# Schematic.net
KiCad netlist of a schematic drawn in EAGLE
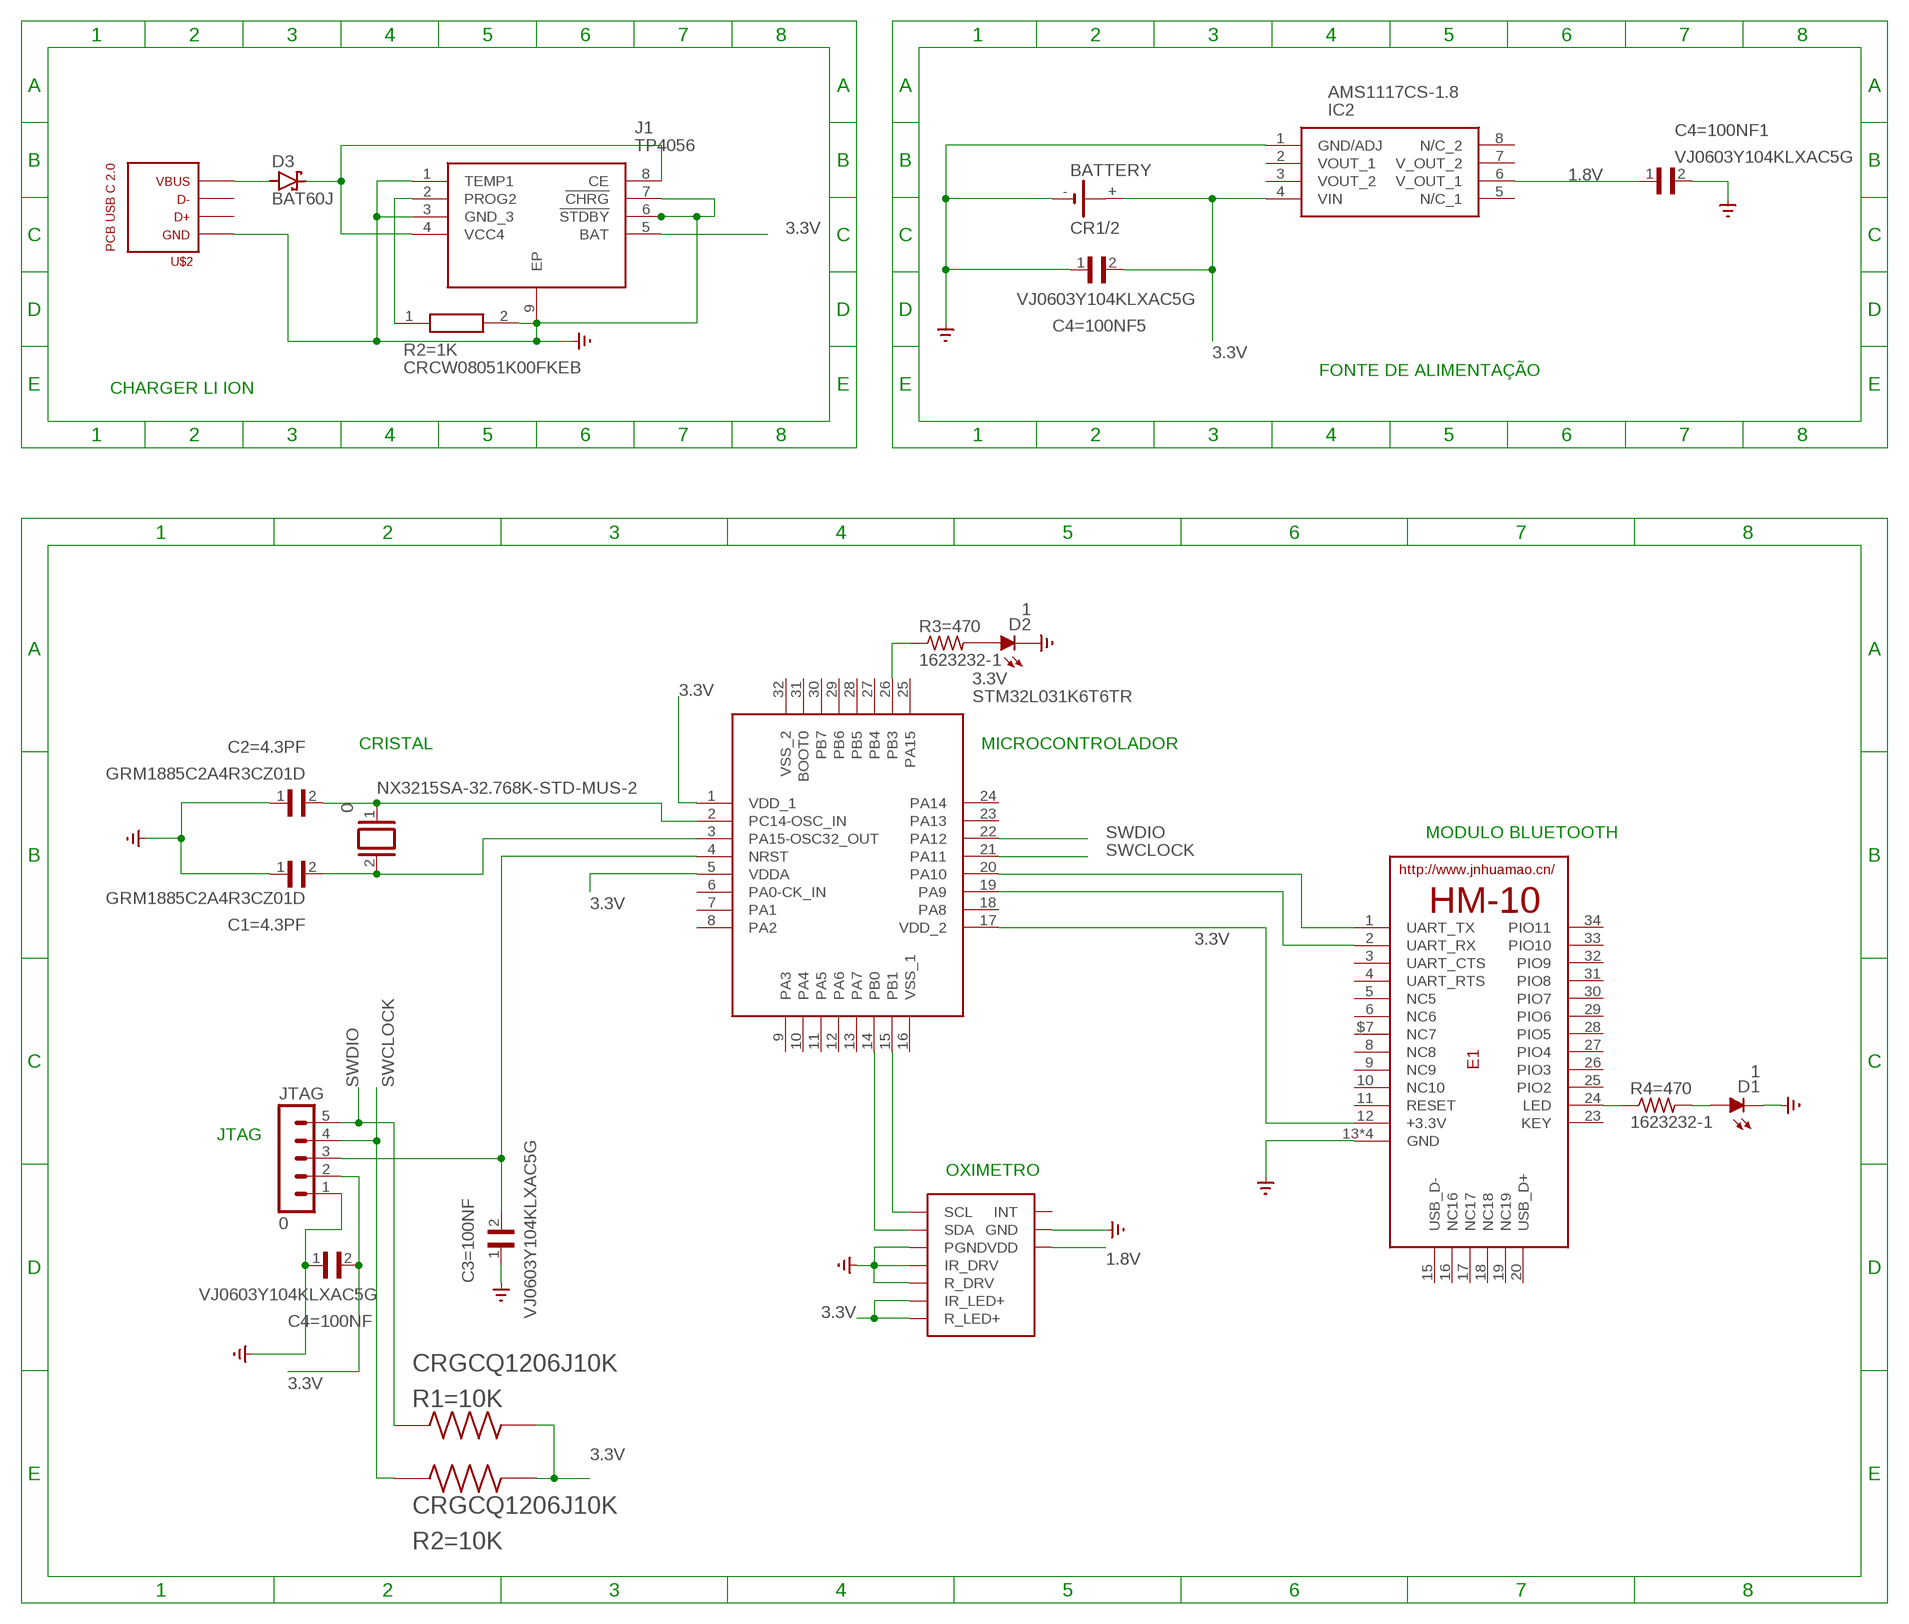
[diagram p0: schematic, sheet 1]

(export (version "E")
  (design (tool "Eeschema 10.0.6"))
  (components
    (comp (ref "3.3V")
      (value "STM32L031K6T6TR")
      (footprint "eagle-import:QFP80P900X900X160-32N")
      (fields (field (name "MOUSER_PART_NUMBER") "511-STM32L031K6T6TR"))
      (libsource (lib "eagle-import") (part "STM32L031K6T6TR"))
    )
    (comp (ref "BATTERY")
      (value "CR1/2")
      (footprint "eagle-import:CR1_2")
      (libsource (lib "eagle-import") (part "CR1/2"))
    )
    (comp (ref "C1=4.3PF")
      (value "GRM1885C2A4R3CZ01D")
      (footprint "eagle-import:CAPC1608X90N")
      (fields (field (name "MF") "Murata"))
      (libsource (lib "eagle-import") (part "GRM1885C2A4R3CZ01D"))
    )
    (comp (ref "C2=4.3PF")
      (value "GRM1885C2A4R3CZ01D")
      (footprint "eagle-import:CAPC1608X90N")
      (fields (field (name "MF") "Murata"))
      (libsource (lib "eagle-import") (part "GRM1885C2A4R3CZ01D"))
    )
    (comp (ref "C3=100NF")
      (value "VJ0603Y104KLXAC5G")
      (footprint "eagle-import:CAPC1608X92N")
      (fields (field (name "MF") "Vishay"))
      (libsource (lib "eagle-import") (part "VJ0603Y104KLXAC5G"))
    )
    (comp (ref "C4=100NF")
      (value "VJ0603Y104KLXAC5G")
      (footprint "eagle-import:CAPC1608X92N")
      (fields (field (name "MF") "Vishay"))
      (libsource (lib "eagle-import") (part "VJ0603Y104KLXAC5G"))
    )
    (comp (ref "C4=100NF1")
      (value "VJ0603Y104KLXAC5G")
      (footprint "eagle-import:CAPC1608X92N")
      (fields (field (name "MF") "Vishay"))
      (libsource (lib "eagle-import") (part "VJ0603Y104KLXAC5G"))
    )
    (comp (ref "C4=100NF5")
      (value "VJ0603Y104KLXAC5G")
      (footprint "eagle-import:CAPC1608X92N")
      (fields (field (name "MF") "Vishay"))
      (libsource (lib "eagle-import") (part "VJ0603Y104KLXAC5G"))
    )
    (comp (ref "D1")
      (value "1")
      (footprint "eagle-import:LED_CHIP-LED0603MP")
      (libsource (lib "eagle-import") (part "LED_LEDCHIP-LED0603MP"))
    )
    (comp (ref "D2")
      (value "1")
      (footprint "eagle-import:LED_CHIP-LED0603MP")
      (libsource (lib "eagle-import") (part "LED_LEDCHIP-LED0603MP"))
    )
    (comp (ref "D3")
      (value "BAT60J")
      (footprint "eagle-import:SOD323_ST")
      (libsource (lib "eagle-import") (part "BAT60J"))
    )
    (comp (ref "E1")
      (value "HM-10-BOARD")
      (footprint "eagle-import:26.9X13X2.2_BOARD")
      (libsource (lib "eagle-import") (part "HM-10-BOARD"))
    )
    (comp (ref "IC2")
      (value "AMS1117CS-1.8")
      (footprint "eagle-import:SOIC127P599X175-8N")
      (libsource (lib "eagle-import") (part "AMS1117CS-1.8"))
    )
    (comp (ref "J1")
      (value "TP4056")
      (footprint "eagle-import:SOIC127P600X175-9N")
      (libsource (lib "eagle-import") (part "TP4056"))
    )
    (comp (ref "JTAG")
      (value "0")
      (footprint "eagle-import:MA05-1")
      (libsource (lib "eagle-import") (part "MA05-1"))
    )
    (comp (ref "NX3215SA-32.768K-STD-MUS-2")
      (value "0")
      (footprint "eagle-import:Q")
      (libsource (lib "eagle-import") (part "XTAL"))
    )
    (comp (ref "R1=10K")
      (value "CRGCQ1206J10K")
      (footprint "eagle-import:RESC3115X65N")
      (fields (field (name "COMMENT") "2-2176344-5") (field (name "MF") "TE Connectivity"))
      (libsource (lib "eagle-import") (part "CRGCQ1206J10K"))
    )
    (comp (ref "R2=1K")
      (value "CRCW08051K00FKEB")
      (footprint "eagle-import:RESC2012X50N")
      (fields (field (name "MOUSER_PART_NUMBER") "71-CRCW08051K00FKEB"))
      (libsource (lib "eagle-import") (part "CRCW08051K00FKEB"))
    )
    (comp (ref "R2=10K")
      (value "CRGCQ1206J10K")
      (footprint "eagle-import:RESC3115X65N")
      (fields (field (name "COMMENT") "2-2176344-5") (field (name "MF") "TE Connectivity"))
      (libsource (lib "eagle-import") (part "CRGCQ1206J10K"))
    )
    (comp (ref "R3=470")
      (value "1623232-1")
      (footprint "eagle-import:RESC2012X65N")
      (fields (field (name "MF") "TE Connectivity") (field (name "TOLERANCE") "1%"))
      (libsource (lib "eagle-import") (part "1623232-1"))
    )
    (comp (ref "R4=470")
      (value "1623232-1")
      (footprint "eagle-import:RESC2012X65N")
      (fields (field (name "MF") "TE Connectivity") (field (name "TOLERANCE") "1%"))
      (libsource (lib "eagle-import") (part "1623232-1"))
    )
    (comp (ref "U$1")
      (value "MAX30100")
      (footprint "eagle-import:MAX30100")
      (libsource (lib "eagle-import") (part "MAX30100"))
    )
    (comp (ref "U$2")
      (value "PCB_USB_C_2.0W_5")
      (footprint "eagle-import:USB_TYPE_C_W_2.0_5")
      (libsource (lib "eagle-import") (part "PCB_USB_C_2.0W_5"))
    )
  )
  (nets
    (net (code "1") (name "/1.8V") (class "Default")
      (node (ref "C4=100NF1") (pin "1") (pinfunction "1_1") (pintype "passive"))
      (node (ref "IC2") (pin "6") (pinfunction "V_OUT_1_6") (pintype "bidirectional"))
      (node (ref "U$1") (pin "11") (pinfunction "VDD_11") (pintype "bidirectional"))
    )
    (net (code "2") (name "/3.3V") (class "Default")
      (node (ref "3.3V") (pin "1") (pinfunction "VDD_1_1") (pintype "bidirectional"))
      (node (ref "3.3V") (pin "17") (pinfunction "VDD_2_17") (pintype "bidirectional"))
      (node (ref "3.3V") (pin "5") (pinfunction "VDDA_5") (pintype "bidirectional"))
      (node (ref "BATTERY") (pin "+") (pinfunction "+_+") (pintype "passive"))
      (node (ref "C4=100NF") (pin "2") (pinfunction "2_2") (pintype "passive"))
      (node (ref "C4=100NF5") (pin "2") (pinfunction "2_2") (pintype "passive"))
      (node (ref "E1") (pin "12") (pinfunction "+3.3V_12") (pintype "bidirectional"))
      (node (ref "IC2") (pin "4") (pinfunction "VIN_4") (pintype "bidirectional"))
      (node (ref "J1") (pin "5") (pinfunction "BAT_5") (pintype "bidirectional"))
      (node (ref "JTAG") (pin "2") (pinfunction "2_2") (pintype "passive"))
      (node (ref "R1=10K") (pin "2") (pinfunction "2_2") (pintype "passive"))
      (node (ref "R2=10K") (pin "2") (pinfunction "2_2") (pintype "passive"))
      (node (ref "U$1") (pin "10") (pinfunction "IR_LED+_10") (pintype "bidirectional"))
      (node (ref "U$1") (pin "9") (pinfunction "R_LED+_9") (pintype "bidirectional"))
    )
    (net (code "3") (name "/SWCLOCK") (class "Default")
      (node (ref "3.3V") (pin "21") (pinfunction "PA11_21") (pintype "bidirectional"))
      (node (ref "JTAG") (pin "4") (pinfunction "4_4") (pintype "passive"))
      (node (ref "R2=10K") (pin "1") (pinfunction "1_1") (pintype "passive"))
    )
    (net (code "4") (name "/SWDIO") (class "Default")
      (node (ref "3.3V") (pin "22") (pinfunction "PA12_22") (pintype "bidirectional"))
      (node (ref "JTAG") (pin "5") (pinfunction "5_5") (pintype "passive"))
      (node (ref "R1=10K") (pin "1") (pinfunction "1_1") (pintype "passive"))
    )
    (net (code "5") (name "Net-(3.3V-NRST)") (class "Default")
      (node (ref "3.3V") (pin "4") (pinfunction "NRST_4") (pintype "bidirectional"))
      (node (ref "C3=100NF") (pin "2") (pinfunction "2_2") (pintype "passive"))
      (node (ref "JTAG") (pin "3") (pinfunction "3_3") (pintype "passive"))
    )
    (net (code "6") (name "Net-(3.3V-PA9)") (class "Default")
      (node (ref "3.3V") (pin "19") (pinfunction "PA9_19") (pintype "bidirectional"))
      (node (ref "E1") (pin "2") (pinfunction "UART_RX_2") (pintype "bidirectional"))
    )
    (net (code "7") (name "Net-(3.3V-PA10)") (class "Default")
      (node (ref "3.3V") (pin "20") (pinfunction "PA10_20") (pintype "bidirectional"))
      (node (ref "E1") (pin "1") (pinfunction "UART_TX_1") (pintype "bidirectional"))
    )
    (net (code "8") (name "Net-(3.3V-PA15-OSC32_OUT)") (class "Default")
      (node (ref "3.3V") (pin "3") (pinfunction "PA15-OSC32_OUT_3") (pintype "bidirectional"))
      (node (ref "C1=4.3PF") (pin "2") (pinfunction "2_2") (pintype "passive"))
      (node (ref "NX3215SA-32.768K-STD-MUS-2") (pin "2") (pinfunction "2_2") (pintype "passive"))
    )
    (net (code "9") (name "Net-(3.3V-PB0)") (class "Default")
      (node (ref "3.3V") (pin "14") (pinfunction "PB0_14") (pintype "bidirectional"))
      (node (ref "U$1") (pin "3") (pinfunction "SDA_3") (pintype "bidirectional"))
    )
    (net (code "10") (name "Net-(3.3V-PB1)") (class "Default")
      (node (ref "3.3V") (pin "15") (pinfunction "PB1_15") (pintype "bidirectional"))
      (node (ref "U$1") (pin "2") (pinfunction "SCL_2") (pintype "bidirectional"))
    )
    (net (code "11") (name "Net-(3.3V-PB3)") (class "Default")
      (node (ref "3.3V") (pin "26") (pinfunction "PB3_26") (pintype "bidirectional"))
      (node (ref "R3=470") (pin "1") (pinfunction "1_1") (pintype "passive"))
    )
    (net (code "12") (name "Net-(3.3V-PC14-OSC_IN)") (class "Default")
      (node (ref "3.3V") (pin "2") (pinfunction "PC14-OSC_IN_2") (pintype "bidirectional"))
      (node (ref "C2=4.3PF") (pin "2") (pinfunction "2_2") (pintype "passive"))
      (node (ref "NX3215SA-32.768K-STD-MUS-2") (pin "1") (pinfunction "1_1") (pintype "passive"))
    )
    (net (code "13") (name "Net-(D1-PadA)") (class "Default")
      (node (ref "D1") (pin "A") (pinfunction "A_A") (pintype "passive"))
      (node (ref "R4=470") (pin "2") (pinfunction "2_2") (pintype "passive"))
    )
    (net (code "14") (name "Net-(D2-PadA)") (class "Default")
      (node (ref "D2") (pin "A") (pinfunction "A_A") (pintype "passive"))
      (node (ref "R3=470") (pin "2") (pinfunction "2_2") (pintype "passive"))
    )
    (net (code "15") (name "Net-(D3-PadA)") (class "Default")
      (node (ref "D3") (pin "A") (pinfunction "A_A") (pintype "passive"))
      (node (ref "U$2") (pin "GND") (pinfunction "GND_GND") (pintype "bidirectional"))
    )
    (net (code "16") (name "Net-(E1-LED)") (class "Default")
      (node (ref "E1") (pin "24") (pinfunction "LED_24") (pintype "bidirectional"))
      (node (ref "R4=470") (pin "1") (pinfunction "1_1") (pintype "passive"))
    )
    (net (code "17") (name "Net-(J1-CE)") (class "Default")
      (node (ref "D3") (pin "C") (pinfunction "C_C") (pintype "passive"))
      (node (ref "J1") (pin "4") (pinfunction "VCC4_4") (pintype "bidirectional"))
      (node (ref "J1") (pin "8") (pinfunction "CE_8") (pintype "bidirectional"))
    )
    (net (code "18") (name "Net-(J1-PROG2)") (class "Default")
      (node (ref "J1") (pin "2") (pinfunction "PROG2_2") (pintype "bidirectional"))
      (node (ref "R2=1K") (pin "1") (pinfunction "1_1") (pintype "bidirectional"))
    )
    (net (code "19") (name "SUPPLY0_GND_") (class "Default")
      (node (ref "BATTERY") (pin "-") (pinfunction "-_-") (pintype "passive"))
      (node (ref "C1=4.3PF") (pin "1") (pinfunction "1_1") (pintype "passive"))
      (node (ref "C2=4.3PF") (pin "1") (pinfunction "1_1") (pintype "passive"))
      (node (ref "C3=100NF") (pin "1") (pinfunction "1_1") (pintype "passive"))
      (node (ref "C4=100NF") (pin "1") (pinfunction "1_1") (pintype "passive"))
      (node (ref "C4=100NF1") (pin "2") (pinfunction "2_2") (pintype "passive"))
      (node (ref "C4=100NF5") (pin "1") (pinfunction "1_1") (pintype "passive"))
      (node (ref "D1") (pin "C") (pinfunction "C_C") (pintype "passive"))
      (node (ref "D2") (pin "C") (pinfunction "C_C") (pintype "passive"))
      (node (ref "E1") (pin "13") (pinfunction "GND_13") (pintype "bidirectional"))
      (node (ref "E1") (pin "14") (pinfunction "GND_14") (pintype "bidirectional"))
      (node (ref "E1") (pin "21") (pinfunction "GND_21") (pintype "bidirectional"))
      (node (ref "E1") (pin "22") (pinfunction "GND_22") (pintype "bidirectional"))
      (node (ref "IC2") (pin "1") (pinfunction "GND/ADJ_1") (pintype "bidirectional"))
      (node (ref "J1") (pin "1") (pinfunction "TEMP1_1") (pintype "bidirectional"))
      (node (ref "J1") (pin "3") (pinfunction "GND_3_3") (pintype "bidirectional"))
      (node (ref "J1") (pin "6") (pinfunction "~{STDBY}_6") (pintype "bidirectional"))
      (node (ref "J1") (pin "7") (pinfunction "~{CHRG}_7") (pintype "bidirectional"))
      (node (ref "J1") (pin "9") (pinfunction "EP_9") (pintype "bidirectional"))
      (node (ref "JTAG") (pin "1") (pinfunction "1_1") (pintype "passive"))
      (node (ref "R2=1K") (pin "2") (pinfunction "2_2") (pintype "bidirectional"))
      (node (ref "U$1") (pin "12") (pinfunction "GND_12") (pintype "bidirectional"))
      (node (ref "U$1") (pin "4") (pinfunction "PGND_4") (pintype "bidirectional"))
      (node (ref "U$1") (pin "5") (pinfunction "IR_DRV_5") (pintype "bidirectional"))
      (node (ref "U$1") (pin "6") (pinfunction "R_DRV_6") (pintype "bidirectional"))
      (node (ref "U$2") (pin "VBUS") (pinfunction "VBUS_VBUS") (pintype "bidirectional"))
    )
    (net (code "20") (name "unconnected-(3.3V-BOOT0-Pad31)") (class "Default")
      (node (ref "3.3V") (pin "31") (pinfunction "BOOT0_31") (pintype "bidirectional"))
    )
    (net (code "21") (name "unconnected-(3.3V-PA0-CK_IN-Pad6)") (class "Default")
      (node (ref "3.3V") (pin "6") (pinfunction "PA0-CK_IN_6") (pintype "bidirectional"))
    )
    (net (code "22") (name "unconnected-(3.3V-PA1-Pad7)") (class "Default")
      (node (ref "3.3V") (pin "7") (pinfunction "PA1_7") (pintype "bidirectional"))
    )
    (net (code "23") (name "unconnected-(3.3V-PA2-Pad8)") (class "Default")
      (node (ref "3.3V") (pin "8") (pinfunction "PA2_8") (pintype "bidirectional"))
    )
    (net (code "24") (name "unconnected-(3.3V-PA3-Pad9)") (class "Default")
      (node (ref "3.3V") (pin "9") (pinfunction "PA3_9") (pintype "bidirectional"))
    )
    (net (code "25") (name "unconnected-(3.3V-PA4-Pad10)") (class "Default")
      (node (ref "3.3V") (pin "10") (pinfunction "PA4_10") (pintype "bidirectional"))
    )
    (net (code "26") (name "unconnected-(3.3V-PA5-Pad11)") (class "Default")
      (node (ref "3.3V") (pin "11") (pinfunction "PA5_11") (pintype "bidirectional"))
    )
    (net (code "27") (name "unconnected-(3.3V-PA6-Pad12)") (class "Default")
      (node (ref "3.3V") (pin "12") (pinfunction "PA6_12") (pintype "bidirectional"))
    )
    (net (code "28") (name "unconnected-(3.3V-PA7-Pad13)") (class "Default")
      (node (ref "3.3V") (pin "13") (pinfunction "PA7_13") (pintype "bidirectional"))
    )
    (net (code "29") (name "unconnected-(3.3V-PA8-Pad18)") (class "Default")
      (node (ref "3.3V") (pin "18") (pinfunction "PA8_18") (pintype "bidirectional"))
    )
    (net (code "30") (name "unconnected-(3.3V-PA13-Pad23)") (class "Default")
      (node (ref "3.3V") (pin "23") (pinfunction "PA13_23") (pintype "bidirectional"))
    )
    (net (code "31") (name "unconnected-(3.3V-PA14-Pad24)") (class "Default")
      (node (ref "3.3V") (pin "24") (pinfunction "PA14_24") (pintype "bidirectional"))
    )
    (net (code "32") (name "unconnected-(3.3V-PA15-Pad25)") (class "Default")
      (node (ref "3.3V") (pin "25") (pinfunction "PA15_25") (pintype "bidirectional"))
    )
    (net (code "33") (name "unconnected-(3.3V-PB4-Pad27)") (class "Default")
      (node (ref "3.3V") (pin "27") (pinfunction "PB4_27") (pintype "bidirectional"))
    )
    (net (code "34") (name "unconnected-(3.3V-PB5-Pad28)") (class "Default")
      (node (ref "3.3V") (pin "28") (pinfunction "PB5_28") (pintype "bidirectional"))
    )
    (net (code "35") (name "unconnected-(3.3V-PB6-Pad29)") (class "Default")
      (node (ref "3.3V") (pin "29") (pinfunction "PB6_29") (pintype "bidirectional"))
    )
    (net (code "36") (name "unconnected-(3.3V-PB7-Pad30)") (class "Default")
      (node (ref "3.3V") (pin "30") (pinfunction "PB7_30") (pintype "bidirectional"))
    )
    (net (code "37") (name "unconnected-(3.3V-VSS_1-Pad16)") (class "Default")
      (node (ref "3.3V") (pin "16") (pinfunction "VSS_1_16") (pintype "bidirectional"))
    )
    (net (code "38") (name "unconnected-(3.3V-VSS_2-Pad32)") (class "Default")
      (node (ref "3.3V") (pin "32") (pinfunction "VSS_2_32") (pintype "bidirectional"))
    )
    (net (code "39") (name "unconnected-(BATTERY-+-Pad+@1)") (class "Default")
      (node (ref "BATTERY") (pin "+@1") (pinfunction "+_+@1") (pintype "passive"))
    )
    (net (code "40") (name "unconnected-(E1-KEY-Pad23)") (class "Default")
      (node (ref "E1") (pin "23") (pinfunction "KEY_23") (pintype "bidirectional"))
    )
    (net (code "41") (name "unconnected-(E1-NC5-Pad5)") (class "Default")
      (node (ref "E1") (pin "5") (pinfunction "NC5_5") (pintype "bidirectional"))
    )
    (net (code "42") (name "unconnected-(E1-NC6-Pad6)") (class "Default")
      (node (ref "E1") (pin "6") (pinfunction "NC6_6") (pintype "bidirectional"))
    )
    (net (code "43") (name "unconnected-(E1-NC7-Pad$7)") (class "Default")
      (node (ref "E1") (pin "$7") (pinfunction "NC7_$7") (pintype "bidirectional"))
    )
    (net (code "44") (name "unconnected-(E1-NC8-Pad8)") (class "Default")
      (node (ref "E1") (pin "8") (pinfunction "NC8_8") (pintype "bidirectional"))
    )
    (net (code "45") (name "unconnected-(E1-NC9-Pad9)") (class "Default")
      (node (ref "E1") (pin "9") (pinfunction "NC9_9") (pintype "bidirectional"))
    )
    (net (code "46") (name "unconnected-(E1-NC10-Pad10)") (class "Default")
      (node (ref "E1") (pin "10") (pinfunction "NC10_10") (pintype "bidirectional"))
    )
    (net (code "47") (name "unconnected-(E1-NC16-Pad16)") (class "Default")
      (node (ref "E1") (pin "16") (pinfunction "NC16_16") (pintype "bidirectional"))
    )
    (net (code "48") (name "unconnected-(E1-NC17-Pad17)") (class "Default")
      (node (ref "E1") (pin "17") (pinfunction "NC17_17") (pintype "bidirectional"))
    )
    (net (code "49") (name "unconnected-(E1-NC18-Pad18)") (class "Default")
      (node (ref "E1") (pin "18") (pinfunction "NC18_18") (pintype "bidirectional"))
    )
    (net (code "50") (name "unconnected-(E1-NC19-Pad19)") (class "Default")
      (node (ref "E1") (pin "19") (pinfunction "NC19_19") (pintype "bidirectional"))
    )
    (net (code "51") (name "unconnected-(E1-PIO2-Pad25)") (class "Default")
      (node (ref "E1") (pin "25") (pinfunction "PIO2_25") (pintype "bidirectional"))
    )
    (net (code "52") (name "unconnected-(E1-PIO3-Pad26)") (class "Default")
      (node (ref "E1") (pin "26") (pinfunction "PIO3_26") (pintype "bidirectional"))
    )
    (net (code "53") (name "unconnected-(E1-PIO4-Pad27)") (class "Default")
      (node (ref "E1") (pin "27") (pinfunction "PIO4_27") (pintype "bidirectional"))
    )
    (net (code "54") (name "unconnected-(E1-PIO5-Pad28)") (class "Default")
      (node (ref "E1") (pin "28") (pinfunction "PIO5_28") (pintype "bidirectional"))
    )
    (net (code "55") (name "unconnected-(E1-PIO6-Pad29)") (class "Default")
      (node (ref "E1") (pin "29") (pinfunction "PIO6_29") (pintype "bidirectional"))
    )
    (net (code "56") (name "unconnected-(E1-PIO7-Pad30)") (class "Default")
      (node (ref "E1") (pin "30") (pinfunction "PIO7_30") (pintype "bidirectional"))
    )
    (net (code "57") (name "unconnected-(E1-PIO8-Pad31)") (class "Default")
      (node (ref "E1") (pin "31") (pinfunction "PIO8_31") (pintype "bidirectional"))
    )
    (net (code "58") (name "unconnected-(E1-PIO9-Pad32)") (class "Default")
      (node (ref "E1") (pin "32") (pinfunction "PIO9_32") (pintype "bidirectional"))
    )
    (net (code "59") (name "unconnected-(E1-PIO10-Pad33)") (class "Default")
      (node (ref "E1") (pin "33") (pinfunction "PIO10_33") (pintype "bidirectional"))
    )
    (net (code "60") (name "unconnected-(E1-PIO11-Pad34)") (class "Default")
      (node (ref "E1") (pin "34") (pinfunction "PIO11_34") (pintype "bidirectional"))
    )
    (net (code "61") (name "unconnected-(E1-RESET-Pad11)") (class "Default")
      (node (ref "E1") (pin "11") (pinfunction "RESET_11") (pintype "bidirectional"))
    )
    (net (code "62") (name "unconnected-(E1-UART_CTS-Pad3)") (class "Default")
      (node (ref "E1") (pin "3") (pinfunction "UART_CTS_3") (pintype "bidirectional"))
    )
    (net (code "63") (name "unconnected-(E1-UART_RTS-Pad4)") (class "Default")
      (node (ref "E1") (pin "4") (pinfunction "UART_RTS_4") (pintype "bidirectional"))
    )
    (net (code "64") (name "unconnected-(E1-USB_D+-Pad20)") (class "Default")
      (node (ref "E1") (pin "20") (pinfunction "USB_D+_20") (pintype "bidirectional"))
    )
    (net (code "65") (name "unconnected-(E1-USB_D--Pad15)") (class "Default")
      (node (ref "E1") (pin "15") (pinfunction "USB_D-_15") (pintype "bidirectional"))
    )
    (net (code "66") (name "unconnected-(IC2-N{slash}C_1-Pad5)") (class "Default")
      (node (ref "IC2") (pin "5") (pinfunction "N/C_1_5") (pintype "bidirectional"))
    )
    (net (code "67") (name "unconnected-(IC2-N{slash}C_2-Pad8)") (class "Default")
      (node (ref "IC2") (pin "8") (pinfunction "N/C_2_8") (pintype "bidirectional"))
    )
    (net (code "68") (name "unconnected-(IC2-VOUT_1-Pad2)") (class "Default")
      (node (ref "IC2") (pin "2") (pinfunction "VOUT_1_2") (pintype "bidirectional"))
    )
    (net (code "69") (name "unconnected-(IC2-VOUT_2-Pad3)") (class "Default")
      (node (ref "IC2") (pin "3") (pinfunction "VOUT_2_3") (pintype "bidirectional"))
    )
    (net (code "70") (name "unconnected-(IC2-V_OUT_2-Pad7)") (class "Default")
      (node (ref "IC2") (pin "7") (pinfunction "V_OUT_2_7") (pintype "bidirectional"))
    )
    (net (code "71") (name "unconnected-(U$1-INT-Pad13)") (class "Default")
      (node (ref "U$1") (pin "13") (pinfunction "INT_13") (pintype "bidirectional"))
    )
    (net (code "72") (name "unconnected-(U$2-PadD+)") (class "Default")
      (node (ref "U$2") (pin "D+") (pinfunction "D+_D+") (pintype "bidirectional"))
    )
    (net (code "73") (name "unconnected-(U$2-PadD-)") (class "Default")
      (node (ref "U$2") (pin "D-") (pinfunction "D-_D-") (pintype "bidirectional"))
    )
  )
)
